# LimitSwitch.net
KiCad netlist of a schematic drawn in EAGLE
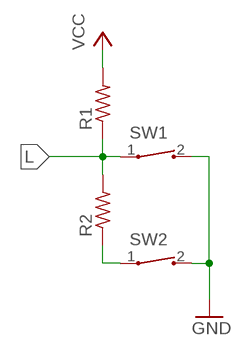
[diagram p0: schematic, sheet 1]

(export (version "E")
  (design (tool "Eeschema 10.0.6"))
  (components
    (comp (ref "R1")
      (value "R-US_0204/7")
      (footprint "eagle-import:0204_7")
      (libsource (lib "eagle-import") (part "R-US_0204/7"))
    )
    (comp (ref "R2")
      (value "R-US_0204/7")
      (footprint "eagle-import:0204_7")
      (libsource (lib "eagle-import") (part "R-US_0204/7"))
    )
    (comp (ref "SW1")
      (value "CT10-XXXX-A2")
      (footprint "eagle-import:CT10-XXXX-A2")
      (libsource (lib "eagle-import") (part "CT10-XXXX-A2"))
    )
    (comp (ref "SW2")
      (value "CT10-XXXX-A2")
      (footprint "eagle-import:CT10-XXXX-A2")
      (libsource (lib "eagle-import") (part "CT10-XXXX-A2"))
    )
  )
  (nets
    (net (code "1") (name "GND") (class "Default")
      (node (ref "SW1") (pin "2") (pinfunction "2_2") (pintype "passive"))
      (node (ref "SW2") (pin "2") (pinfunction "2_2") (pintype "passive"))
    )
    (net (code "2") (name "L") (class "Default")
      (node (ref "R1") (pin "1") (pinfunction "1_1") (pintype "passive"))
      (node (ref "R2") (pin "2") (pinfunction "2_2") (pintype "passive"))
      (node (ref "SW1") (pin "1") (pinfunction "1_1") (pintype "passive"))
    )
    (net (code "3") (name "Net-(R2-Pad1)") (class "Default")
      (node (ref "R2") (pin "1") (pinfunction "1_1") (pintype "passive"))
      (node (ref "SW2") (pin "1") (pinfunction "1_1") (pintype "passive"))
    )
    (net (code "4") (name "VCC") (class "Default")
      (node (ref "R1") (pin "2") (pinfunction "2_2") (pintype "passive"))
    )
  )
)
